# DisplayPort_CON.net
KiCad netlist of a schematic drawn in Altium Designer
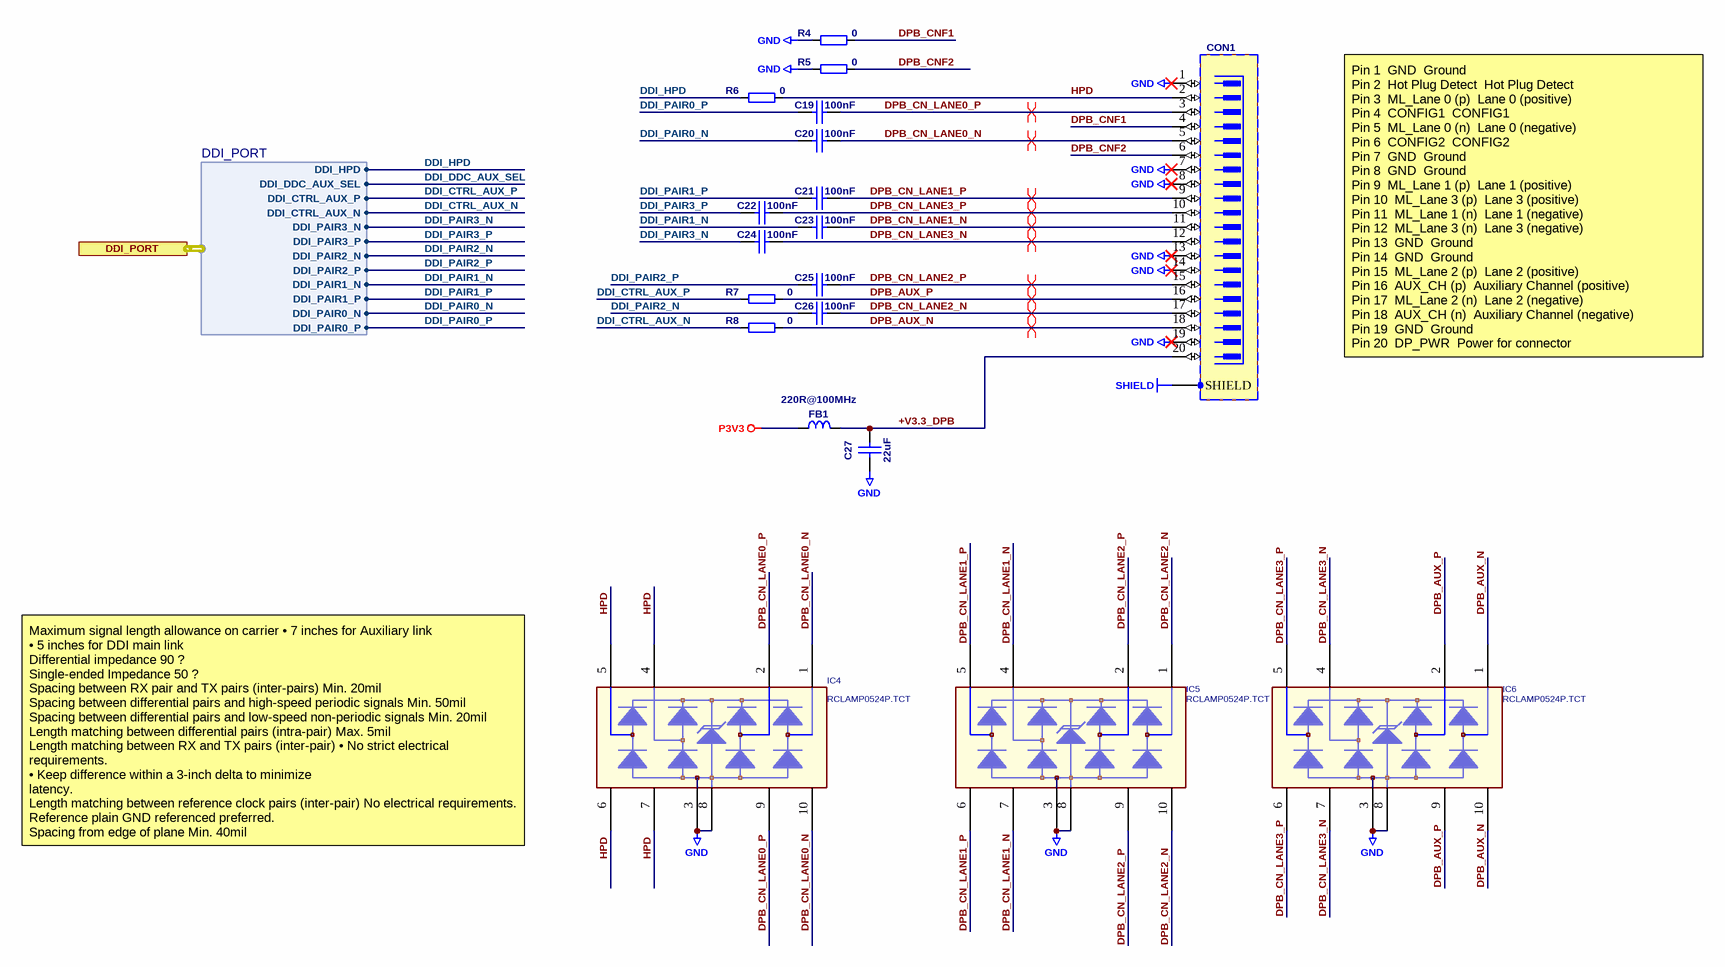
[diagram p0: DisplayPort_CON.SchDoc]

(export (version "E")
  (design (tool "Eeschema 10.0.6"))
  (components
    (comp (ref "C19")
      (value "100nF")
      (footprint "CAPC1005X55N")
      (description "Non-polarised capacitor")
      (fields
        (field (name "PART NUMBER") "CC0402_100NF_16V_10%_X7R")
        (field (name "VOLTAGE") "16V")
        (field (name "AUTHOR") "CERN DEM JLC")
      )
      (libsource (lib "Capacitors") (part "Capacitor - non polarized"))
    )
    (comp (ref "C20")
      (value "100nF")
      (footprint "CAPC1005X55N")
      (description "Non-polarised capacitor")
      (fields
        (field (name "PART NUMBER") "CC0402_100NF_16V_10%_X7R")
        (field (name "VOLTAGE") "16V")
        (field (name "AUTHOR") "CERN DEM JLC")
      )
      (libsource (lib "Capacitors") (part "Capacitor - non polarized"))
    )
    (comp (ref "C21")
      (value "100nF")
      (footprint "CAPC1005X55N")
      (description "Non-polarised capacitor")
      (fields
        (field (name "PART NUMBER") "CC0402_100NF_16V_10%_X7R")
        (field (name "VOLTAGE") "16V")
        (field (name "AUTHOR") "CERN DEM JLC")
      )
      (libsource (lib "Capacitors") (part "Capacitor - non polarized"))
    )
    (comp (ref "C22")
      (value "100nF")
      (footprint "CAPC1005X55N")
      (description "Non-polarised capacitor")
      (fields
        (field (name "PART NUMBER") "CC0402_100NF_16V_10%_X7R")
        (field (name "VOLTAGE") "16V")
        (field (name "AUTHOR") "CERN DEM JLC")
      )
      (libsource (lib "Capacitors") (part "Capacitor - non polarized"))
    )
    (comp (ref "C23")
      (value "100nF")
      (footprint "CAPC1005X55N")
      (description "Non-polarised capacitor")
      (fields
        (field (name "PART NUMBER") "CC0402_100NF_16V_10%_X7R")
        (field (name "VOLTAGE") "16V")
        (field (name "AUTHOR") "CERN DEM JLC")
      )
      (libsource (lib "Capacitors") (part "Capacitor - non polarized"))
    )
    (comp (ref "C24")
      (value "100nF")
      (footprint "CAPC1005X55N")
      (description "Non-polarised capacitor")
      (fields
        (field (name "PART NUMBER") "CC0402_100NF_16V_10%_X7R")
        (field (name "VOLTAGE") "16V")
        (field (name "AUTHOR") "CERN DEM JLC")
      )
      (libsource (lib "Capacitors") (part "Capacitor - non polarized"))
    )
    (comp (ref "C25")
      (value "100nF")
      (footprint "CAPC1005X55N")
      (description "Non-polarised capacitor")
      (fields
        (field (name "PART NUMBER") "CC0402_100NF_16V_10%_X7R")
        (field (name "VOLTAGE") "16V")
        (field (name "AUTHOR") "CERN DEM JLC")
      )
      (libsource (lib "Capacitors") (part "Capacitor - non polarized"))
    )
    (comp (ref "C26")
      (value "100nF")
      (footprint "CAPC1005X55N")
      (description "Non-polarised capacitor")
      (fields
        (field (name "PART NUMBER") "CC0402_100NF_16V_10%_X7R")
        (field (name "VOLTAGE") "16V")
        (field (name "AUTHOR") "CERN DEM JLC")
      )
      (libsource (lib "Capacitors") (part "Capacitor - non polarized"))
    )
    (comp (ref "C27")
      (value "22uF")
      (footprint "CAPC2012X135N")
      (description "Non-polarised capacitor")
      (fields
        (field (name "MANUFACTURER PART NUMBER") "CC0805_22UF_16V_10%_X5R")
        (field (name "MANUFACTURER") "GENERIC")
        (field (name "AUTHOR") "CERN DEM JLC")
      )
      (libsource (lib "Capacitors") (part "Capacitor - non polarized"))
    )
    (comp (ref "CON1")
      (value "Mini DP")
      (footprint "MULTICOMP_64L020S-3x1N-B")
      (description "Connector Mini DisplayPort 20 Male + 1 Shield")
      (fields
        (field (name "PART NUMBER") "MULTICOMP_64L020S-331N-B")
        (field (name "MANUFACTURER") "FREEPORT")
        (field (name "AUTHOR") "CERN DEM JMW")
      )
      (libsource (lib "Connectors") (part "Connector Mini DisplayPort 20 Male + 1 Shield"))
    )
    (comp (ref "FB1")
      (value "220R@100MHz")
      (footprint "0603L")
      (description "Inductor")
      (fields
        (field (name "PART NUMBER") "IND0805_MURATA_BLM21PG221SN1D")
        (field (name "POWER") "2A")
        (field (name "AUTHOR") "CERN DEM JLC")
      )
      (libsource (lib "Inductors & Transformers") (part "Inductor"))
    )
    (comp (ref "IC4")
      (value "RCLAMP0524P.TCT")
      (description "DIODE,RCLAMP0524P,SEMTECH")
      (libsource (lib "LIBRARY_SCH") (part "D_TVS_RCLAMP0524P"))
    )
    (comp (ref "IC5")
      (value "RCLAMP0524P.TCT")
      (description "DIODE,RCLAMP0524P,SEMTECH")
      (libsource (lib "LIBRARY_SCH") (part "D_TVS_RCLAMP0524P"))
    )
    (comp (ref "IC6")
      (value "RCLAMP0524P.TCT")
      (description "DIODE,RCLAMP0524P,SEMTECH")
      (libsource (lib "LIBRARY_SCH") (part "D_TVS_RCLAMP0524P"))
    )
    (comp (ref "R4")
      (value "0")
      (footprint "RESC1005X40N")
      (description "Resistor")
      (fields
        (field (name "PART NUMBER") "R0402_0R_JUMPER")
        (field (name "MANUFACTURER") "GENERIC")
        (field (name "AUTHOR") "CERN DEM JLC")
      )
      (libsource (lib "Resistors") (part "Resistor"))
    )
    (comp (ref "R5")
      (value "0")
      (footprint "RESC1005X40N")
      (description "Resistor")
      (fields
        (field (name "PART NUMBER") "R0402_0R_JUMPER")
        (field (name "MANUFACTURER") "GENERIC")
        (field (name "AUTHOR") "CERN DEM JLC")
      )
      (libsource (lib "Resistors") (part "Resistor"))
    )
    (comp (ref "R6")
      (value "0")
      (footprint "RESC1005X40N")
      (description "Resistor")
      (fields
        (field (name "PART NUMBER") "R0402_0R_JUMPER")
        (field (name "MANUFACTURER") "GENERIC")
        (field (name "AUTHOR") "CERN DEM JLC")
      )
      (libsource (lib "Resistors") (part "Resistor"))
    )
    (comp (ref "R7")
      (value "0")
      (footprint "RESC1005X40N")
      (description "Resistor")
      (fields
        (field (name "PART NUMBER") "R0402_0R_JUMPER")
        (field (name "MANUFACTURER") "GENERIC")
        (field (name "AUTHOR") "CERN DEM JLC")
      )
      (libsource (lib "Resistors") (part "Resistor"))
    )
    (comp (ref "R8")
      (value "0")
      (footprint "RESC1005X40N")
      (description "Resistor")
      (fields
        (field (name "PART NUMBER") "R0402_0R_JUMPER")
        (field (name "MANUFACTURER") "GENERIC")
        (field (name "AUTHOR") "CERN DEM JLC")
      )
      (libsource (lib "Resistors") (part "Resistor"))
    )
  )
  (nets
    (net (code "2") (name "/+V3.3_DPB") (class "Default")
      (node (ref "C27") (pin "2") (pinfunction "2_2") (pintype "passive"))
      (node (ref "CON1") (pin "20") (pinfunction "20_20") (pintype "bidirectional"))
      (node (ref "FB1") (pin "2") (pinfunction "2_2") (pintype "passive"))
    )
    (net (code "3") (name "/DDI_CTRL_AUX_N") (class "Default")
      (node (ref "R8") (pin "1") (pinfunction "1_1") (pintype "passive"))
    )
    (net (code "4") (name "/DDI_CTRL_AUX_P") (class "Default")
      (node (ref "R7") (pin "1") (pinfunction "1_1") (pintype "passive"))
    )
    (net (code "6") (name "/DDI_HPD") (class "Default")
      (node (ref "R6") (pin "1") (pinfunction "1_1") (pintype "passive"))
    )
    (net (code "7") (name "/DDI_PAIR0_N") (class "Default")
      (node (ref "C20") (pin "1") (pinfunction "1_1") (pintype "passive"))
    )
    (net (code "8") (name "/DDI_PAIR0_P") (class "Default")
      (node (ref "C19") (pin "1") (pinfunction "1_1") (pintype "passive"))
    )
    (net (code "9") (name "/DDI_PAIR1_N") (class "Default")
      (node (ref "C23") (pin "1") (pinfunction "1_1") (pintype "passive"))
    )
    (net (code "10") (name "/DDI_PAIR1_P") (class "Default")
      (node (ref "C21") (pin "1") (pinfunction "1_1") (pintype "passive"))
    )
    (net (code "11") (name "/DDI_PAIR2_N") (class "Default")
      (node (ref "C26") (pin "1") (pinfunction "1_1") (pintype "passive"))
    )
    (net (code "12") (name "/DDI_PAIR2_P") (class "Default")
      (node (ref "C25") (pin "1") (pinfunction "1_1") (pintype "passive"))
    )
    (net (code "13") (name "/DDI_PAIR3_N") (class "Default")
      (node (ref "C24") (pin "1") (pinfunction "1_1") (pintype "passive"))
    )
    (net (code "14") (name "/DDI_PAIR3_P") (class "Default")
      (node (ref "C22") (pin "1") (pinfunction "1_1") (pintype "passive"))
    )
    (net (code "15") (name "/DPB_AUX_N") (class "Default")
      (node (ref "CON1") (pin "18") (pinfunction "18_18") (pintype "bidirectional"))
      (node (ref "IC6") (pin "1") (pinfunction "1_1") (pintype "passive"))
      (node (ref "IC6") (pin "10") (pinfunction "10_10") (pintype "passive"))
      (node (ref "R8") (pin "2") (pinfunction "2_2") (pintype "passive"))
    )
    (net (code "16") (name "/DPB_AUX_P") (class "Default")
      (node (ref "CON1") (pin "16") (pinfunction "16_16") (pintype "bidirectional"))
      (node (ref "IC6") (pin "2") (pinfunction "2_2") (pintype "passive"))
      (node (ref "IC6") (pin "9") (pinfunction "9_9") (pintype "passive"))
      (node (ref "R7") (pin "2") (pinfunction "2_2") (pintype "passive"))
    )
    (net (code "17") (name "/DPB_CNF1") (class "Default")
      (node (ref "CON1") (pin "4") (pinfunction "4_4") (pintype "bidirectional"))
      (node (ref "R4") (pin "2") (pinfunction "2_2") (pintype "passive"))
    )
    (net (code "18") (name "/DPB_CNF2") (class "Default")
      (node (ref "CON1") (pin "6") (pinfunction "6_6") (pintype "bidirectional"))
      (node (ref "R5") (pin "2") (pinfunction "2_2") (pintype "passive"))
    )
    (net (code "19") (name "/DPB_CN_LANE0_N") (class "Default")
      (node (ref "C20") (pin "2") (pinfunction "2_2") (pintype "passive"))
      (node (ref "CON1") (pin "5") (pinfunction "5_5") (pintype "bidirectional"))
      (node (ref "IC4") (pin "1") (pinfunction "1_1") (pintype "passive"))
      (node (ref "IC4") (pin "10") (pinfunction "10_10") (pintype "passive"))
    )
    (net (code "20") (name "/DPB_CN_LANE0_P") (class "Default")
      (node (ref "C19") (pin "2") (pinfunction "2_2") (pintype "passive"))
      (node (ref "CON1") (pin "3") (pinfunction "3_3") (pintype "bidirectional"))
      (node (ref "IC4") (pin "2") (pinfunction "2_2") (pintype "passive"))
      (node (ref "IC4") (pin "9") (pinfunction "9_9") (pintype "passive"))
    )
    (net (code "21") (name "/DPB_CN_LANE1_N") (class "Default")
      (node (ref "C23") (pin "2") (pinfunction "2_2") (pintype "passive"))
      (node (ref "CON1") (pin "11") (pinfunction "11_11") (pintype "bidirectional"))
      (node (ref "IC5") (pin "4") (pinfunction "4_4") (pintype "passive"))
      (node (ref "IC5") (pin "7") (pinfunction "7_7") (pintype "passive"))
    )
    (net (code "22") (name "/DPB_CN_LANE1_P") (class "Default")
      (node (ref "C21") (pin "2") (pinfunction "2_2") (pintype "passive"))
      (node (ref "CON1") (pin "9") (pinfunction "9_9") (pintype "bidirectional"))
      (node (ref "IC5") (pin "5") (pinfunction "5_5") (pintype "passive"))
      (node (ref "IC5") (pin "6") (pinfunction "6_6") (pintype "passive"))
    )
    (net (code "23") (name "/DPB_CN_LANE2_N") (class "Default")
      (node (ref "C26") (pin "2") (pinfunction "2_2") (pintype "passive"))
      (node (ref "CON1") (pin "17") (pinfunction "17_17") (pintype "bidirectional"))
      (node (ref "IC5") (pin "1") (pinfunction "1_1") (pintype "passive"))
      (node (ref "IC5") (pin "10") (pinfunction "10_10") (pintype "passive"))
    )
    (net (code "24") (name "/DPB_CN_LANE2_P") (class "Default")
      (node (ref "C25") (pin "2") (pinfunction "2_2") (pintype "passive"))
      (node (ref "CON1") (pin "15") (pinfunction "15_15") (pintype "bidirectional"))
      (node (ref "IC5") (pin "2") (pinfunction "2_2") (pintype "passive"))
      (node (ref "IC5") (pin "9") (pinfunction "9_9") (pintype "passive"))
    )
    (net (code "25") (name "/DPB_CN_LANE3_N") (class "Default")
      (node (ref "C24") (pin "2") (pinfunction "2_2") (pintype "passive"))
      (node (ref "CON1") (pin "12") (pinfunction "12_12") (pintype "bidirectional"))
      (node (ref "IC6") (pin "4") (pinfunction "4_4") (pintype "passive"))
      (node (ref "IC6") (pin "7") (pinfunction "7_7") (pintype "passive"))
    )
    (net (code "26") (name "/DPB_CN_LANE3_P") (class "Default")
      (node (ref "C22") (pin "2") (pinfunction "2_2") (pintype "passive"))
      (node (ref "CON1") (pin "10") (pinfunction "10_10") (pintype "bidirectional"))
      (node (ref "IC6") (pin "5") (pinfunction "5_5") (pintype "passive"))
      (node (ref "IC6") (pin "6") (pinfunction "6_6") (pintype "passive"))
    )
    (net (code "27") (name "/HPD") (class "Default")
      (node (ref "CON1") (pin "2") (pinfunction "2_2") (pintype "bidirectional"))
      (node (ref "IC4") (pin "4") (pinfunction "4_4") (pintype "passive"))
      (node (ref "IC4") (pin "5") (pinfunction "5_5") (pintype "passive"))
      (node (ref "IC4") (pin "6") (pinfunction "6_6") (pintype "passive"))
      (node (ref "IC4") (pin "7") (pinfunction "7_7") (pintype "passive"))
      (node (ref "R6") (pin "2") (pinfunction "2_2") (pintype "passive"))
    )
    (net (code "29") (name "GND") (class "Default")
      (node (ref "C27") (pin "1") (pinfunction "1_1") (pintype "passive"))
      (node (ref "CON1") (pin "1") (pinfunction "1_1") (pintype "bidirectional"))
      (node (ref "CON1") (pin "13") (pinfunction "13_13") (pintype "bidirectional"))
      (node (ref "CON1") (pin "14") (pinfunction "14_14") (pintype "bidirectional"))
      (node (ref "CON1") (pin "19") (pinfunction "19_19") (pintype "bidirectional"))
      (node (ref "CON1") (pin "7") (pinfunction "7_7") (pintype "bidirectional"))
      (node (ref "CON1") (pin "8") (pinfunction "8_8") (pintype "bidirectional"))
      (node (ref "IC4") (pin "3") (pinfunction "3_3") (pintype "passive"))
      (node (ref "IC4") (pin "8") (pinfunction "8_8") (pintype "passive"))
      (node (ref "IC5") (pin "3") (pinfunction "3_3") (pintype "passive"))
      (node (ref "IC5") (pin "8") (pinfunction "8_8") (pintype "passive"))
      (node (ref "IC6") (pin "3") (pinfunction "3_3") (pintype "passive"))
      (node (ref "IC6") (pin "8") (pinfunction "8_8") (pintype "passive"))
      (node (ref "R4") (pin "1") (pinfunction "1_1") (pintype "passive"))
      (node (ref "R5") (pin "1") (pinfunction "1_1") (pintype "passive"))
    )
    (net (code "30") (name "P3V3") (class "Default")
      (node (ref "FB1") (pin "1") (pinfunction "1_1") (pintype "passive"))
    )
    (net (code "31") (name "SHIELD") (class "Default")
      (node (ref "CON1") (pin "SHIELD") (pinfunction "SHIELD_SHIELD") (pintype "power_in"))
    )
  )
)
